# DAC_To_LP_Filter.net
KiCad netlist of a schematic drawn in Altium Designer
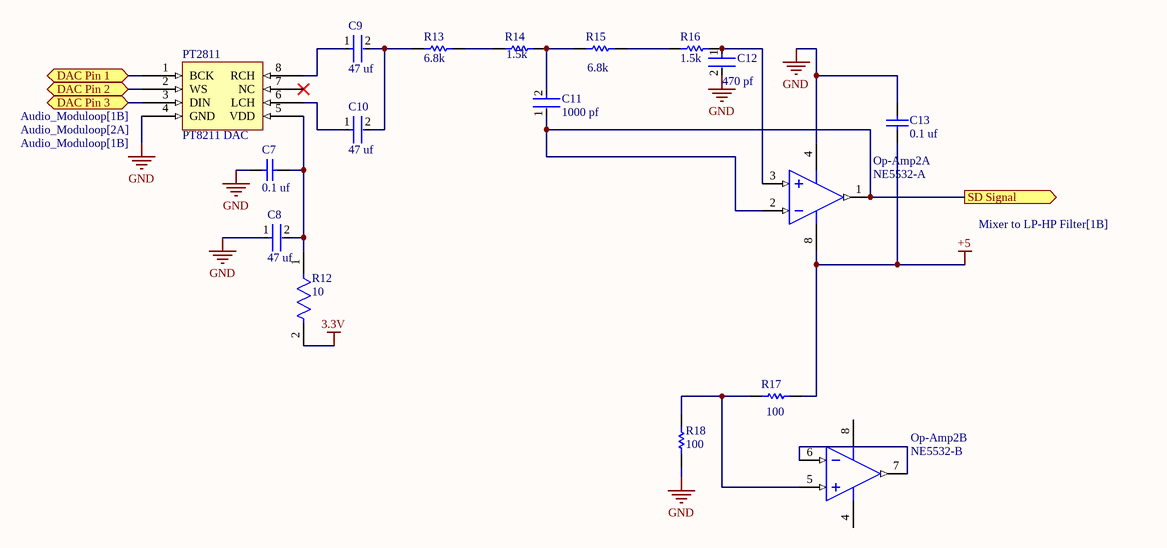
[diagram p0: DAC To LP Filter.SchDoc]

(export (version "E")
  (design (tool "Eeschema 10.0.6"))
  (components
    (comp (ref "C7")
      (value "0.1 uf")
      (footprint "VISH-K104K15X7RF5TL2")
      (description "Ceramic Capacitor, 100 nF, +/- 10%, 50 V, -55 to 125 degC, 2-Pin THD, RoHS, Tape and Reel")
      (fields (field (name "MANUFACTURER") "Vishay") (field (name "TOLERANCE") "±10%"))
      (libsource (lib "Altium Content Vault") (part "CAP-NP-2"))
    )
    (comp (ref "C8")
      (value "47 uf")
      (footprint "FP-RCE2A2-MFG")
      (description "Cap Ceramic 4.7uF 25V X7R ±10% Radial 2.5mm +125°C Automotive Ammo Pack")
      (fields (field (name "TOLERANCE") "10%"))
      (libsource (lib "Altium Content Vault") (part "b4654b650e69147ec39a6b967a45e02"))
    )
    (comp (ref "C9")
      (value "47 uf")
      (footprint "FP-RCE2A2-MFG")
      (description "Cap Ceramic 4.7uF 25V X7R ±10% Radial 2.5mm +125°C Automotive Ammo Pack")
      (fields (field (name "TOLERANCE") "10%"))
      (libsource (lib "Altium Content Vault") (part "b4654b650e69147ec39a6b967a45e02"))
    )
    (comp (ref "C10")
      (value "47 uf")
      (footprint "FP-RCE2A2-MFG")
      (description "Cap Ceramic 4.7uF 25V X7R ±10% Radial 2.5mm +125°C Automotive Ammo Pack")
      (fields (field (name "TOLERANCE") "10%"))
      (libsource (lib "Altium Content Vault") (part "b4654b650e69147ec39a6b967a45e02"))
    )
    (comp (ref "C11")
      (value "1000 pf")
      (footprint "FP-VY1102M35Y5UQ6TV0-MFG")
      (description "CAP CER 1000PF 760VAC Y5U RADIAL")
      (fields (field (name "VOLTAGE") "500V") (field (name "TOLERANCE") "20%"))
      (libsource (lib "Altium Content Vault") (part "6d4d395cd7362dd47ce0157d173177e"))
    )
    (comp (ref "C12")
      (value "470 pf")
      (footprint "FP-F471K33Y5RP6UK5R-MFG")
      (description "CAP CER 470PF 2KV Y5R RADIAL")
      (fields (field (name "TOLERANCE") "10%") (field (name "VOLTAGE") "2kV"))
      (libsource (lib "Altium Content Vault") (part "b4654b650e69147ec39a6b967a45e02"))
    )
    (comp (ref "C13")
      (value "0.1 uf")
      (footprint "AVX-SA115C104KAR")
      (fields (field (name "TOLERANCE") "±10%") (field (name "MANUFACTURER") "AVX"))
      (libsource (lib "Altium Content Vault") (part "CAP-NP-2"))
    )
    (comp (ref "Op-Amp2")
      (value "NE5532-A")
      (footprint "ONSC-SOIC-8-751-07_V")
      (fields (field (name "MANUFACTURER") "On Semiconductor") (field (name "PARTNUMBER") "NE5532AD8R2G"))
      (libsource (lib "Altium Content Vault") (part "ONSC-NE5532-SOIC-8-751-07"))
    )
    (comp (ref "PT2811")
      (value "PT8211 DAC")
      (footprint "SOIC127P602X173-8N")
      (libsource (lib "Ryamgordon") (part "DAC"))
    )
    (comp (ref "R12")
      (value "10")
      (footprint "FP-RN732A-MFG")
      (description "SMD Chip Resistor, Thin Film, 10Ω, 100 V, 0805 [2012 Metric], 100 mW, 0.1%, RN73 Series")
      (fields
        (field (name "MANUFACTURER") "TE Connectivity")
        (field (name "MANUFACTURER PART NUMBER") "RN73C2A10RBTG")
      )
      (libsource (lib "Altium Content Vault") (part "1029c3af85768c4190bb7ad29bc67b5"))
    )
    (comp (ref "R13")
      (value "6.8k")
      (footprint "RESC2013X70X40LL20T20")
      (fields (field (name "MANUFACTURER") "Panasonic") (field (name "PART NUMBER") "ERJ6ENF6801V"))
      (libsource (lib "Altium Content Vault") (part "RES"))
    )
    (comp (ref "R14")
      (value "1.5k")
      (footprint "RESC2013X60X35LL10T20")
      (description "RES 1.50K OHM 1/8W 1% 0805 SMD")
      (fields (field (name "MANUFACTURER") "Yageo") (field (name "PARTNUMBER") "RC0805FR-071K5L"))
      (libsource (lib "Altium Content Vault") (part "RES-2"))
    )
    (comp (ref "R15")
      (value "6.8k")
      (footprint "RESC2013X70X40LL20T20")
      (fields (field (name "MANUFACTURER") "Panasonic") (field (name "PART NUMBER") "ERJ6ENF6801V"))
      (libsource (lib "Altium Content Vault") (part "RES"))
    )
    (comp (ref "R16")
      (value "1.5k")
      (footprint "RESC2013X60X35LL10T20")
      (description "RES 1.50K OHM 1/8W 1% 0805 SMD")
      (fields (field (name "MANUFACTURER") "Yageo") (field (name "PARTNUMBER") "RC0805FR-071K5L"))
      (libsource (lib "Altium Content Vault") (part "RES-2"))
    )
    (comp (ref "R17")
      (value "100")
      (footprint "RESC2013X60X40ML20T25")
      (fields (field (name "MANUFACTURER") "Panasonic") (field (name "PART NUMBER") "ERA6AEB101V"))
      (libsource (lib "Altium Content Vault") (part "RES"))
    )
    (comp (ref "R18")
      (value "100")
      (footprint "RESC2013X60X40ML20T25")
      (fields (field (name "MANUFACTURER") "Panasonic") (field (name "PART NUMBER") "ERA6AEB101V"))
      (libsource (lib "Altium Content Vault") (part "RES"))
    )
  )
  (nets
    (net (code "1") (name "+5") (class "Default")
      (node (ref "C13") (pin "1") (pinfunction "1_1") (pintype "passive"))
      (node (ref "Op-Amp2") (pin "8") (pinfunction "V+_8") (pintype "power_in"))
      (node (ref "R17") (pin "2") (pinfunction "2_2") (pintype "passive"))
    )
    (net (code "2") (name "/DAC Pin 1") (class "Default")
      (node (ref "PT2811") (pin "1") (pinfunction "BCK_1") (pintype "input"))
    )
    (net (code "3") (name "/DAC Pin 2") (class "Default")
      (node (ref "PT2811") (pin "2") (pinfunction "WS_2") (pintype "input"))
    )
    (net (code "4") (name "/DAC Pin 3") (class "Default")
      (node (ref "PT2811") (pin "3") (pinfunction "DIN_3") (pintype "input"))
    )
    (net (code "5") (name "/SD Signal") (class "Default")
      (node (ref "C11") (pin "1") (pinfunction "1_1") (pintype "passive"))
      (node (ref "Op-Amp2") (pin "1") (pinfunction "OUTA_1") (pintype "output"))
      (node (ref "Op-Amp2") (pin "2") (pinfunction "INA-_2") (pintype "input"))
    )
    (net (code "6") (name "3.3V") (class "Default")
      (node (ref "R12") (pin "2") (pinfunction "2_2") (pintype "passive"))
    )
    (net (code "7") (name "GND") (class "Default")
      (node (ref "C12") (pin "2") (pinfunction "2_2") (pintype "passive"))
      (node (ref "C13") (pin "2") (pinfunction "2_2") (pintype "passive"))
      (node (ref "C7") (pin "2") (pinfunction "2_2") (pintype "passive"))
      (node (ref "C8") (pin "1") (pinfunction "1_1") (pintype "passive"))
      (node (ref "Op-Amp2") (pin "4") (pinfunction "V-_4") (pintype "power_in"))
      (node (ref "PT2811") (pin "4") (pinfunction "GND_4") (pintype "input"))
      (node (ref "R18") (pin "1") (pinfunction "1_1") (pintype "passive"))
    )
    (net (code "8") (name "Net-(C10-Pad2)") (class "Default")
      (node (ref "C10") (pin "2") (pinfunction "2_2") (pintype "passive"))
      (node (ref "C9") (pin "2") (pinfunction "2_2") (pintype "passive"))
      (node (ref "R13") (pin "1") (pinfunction "1_1") (pintype "passive"))
    )
    (net (code "9") (name "Net-(C11-Pad2)") (class "Default")
      (node (ref "C11") (pin "2") (pinfunction "2_2") (pintype "passive"))
      (node (ref "R14") (pin "2") (pinfunction "2_2") (pintype "passive"))
      (node (ref "R15") (pin "1") (pinfunction "1_1") (pintype "passive"))
    )
    (net (code "10") (name "Net-(Op-Amp2A-INA+)") (class "Default")
      (node (ref "C12") (pin "1") (pinfunction "1_1") (pintype "passive"))
      (node (ref "Op-Amp2") (pin "3") (pinfunction "INA+_3") (pintype "input"))
      (node (ref "R16") (pin "2") (pinfunction "2_2") (pintype "passive"))
    )
    (net (code "11") (name "Net-(Op-Amp2B-INB+)") (class "Default")
      (node (ref "Op-Amp2") (pin "5") (pinfunction "INB+_5") (pintype "input"))
      (node (ref "R17") (pin "1") (pinfunction "1_1") (pintype "passive"))
      (node (ref "R18") (pin "2") (pinfunction "2_2") (pintype "passive"))
    )
    (net (code "12") (name "Net-(Op-Amp2B-INB-)") (class "Default")
      (node (ref "Op-Amp2") (pin "6") (pinfunction "INB-_6") (pintype "input"))
      (node (ref "Op-Amp2") (pin "7") (pinfunction "OUTB_7") (pintype "output"))
    )
    (net (code "13") (name "Net-(PT2811-LCH)") (class "Default")
      (node (ref "C10") (pin "1") (pinfunction "1_1") (pintype "passive"))
      (node (ref "PT2811") (pin "6") (pinfunction "LCH_6") (pintype "input"))
    )
    (net (code "14") (name "Net-(PT2811-RCH)") (class "Default")
      (node (ref "C9") (pin "1") (pinfunction "1_1") (pintype "passive"))
      (node (ref "PT2811") (pin "8") (pinfunction "RCH_8") (pintype "input"))
    )
    (net (code "15") (name "Net-(PT2811-VDD)") (class "Default")
      (node (ref "C7") (pin "1") (pinfunction "1_1") (pintype "passive"))
      (node (ref "C8") (pin "2") (pinfunction "2_2") (pintype "passive"))
      (node (ref "PT2811") (pin "5") (pinfunction "VDD_5") (pintype "input"))
      (node (ref "R12") (pin "1") (pinfunction "1_1") (pintype "passive"))
    )
    (net (code "16") (name "Net-(R13-Pad2)") (class "Default")
      (node (ref "R13") (pin "2") (pinfunction "2_2") (pintype "passive"))
      (node (ref "R14") (pin "1") (pinfunction "1_1") (pintype "passive"))
    )
    (net (code "17") (name "Net-(R15-Pad2)") (class "Default")
      (node (ref "R15") (pin "2") (pinfunction "2_2") (pintype "passive"))
      (node (ref "R16") (pin "1") (pinfunction "1_1") (pintype "passive"))
    )
    (net (code "18") (name "unconnected-(Op-Amp2B-V+-Pad8)") (class "Default")
      (node (ref "Op-Amp2") (pin "8") (pinfunction "V+_8") (pintype "power_in"))
    )
    (net (code "19") (name "unconnected-(Op-Amp2B-V--Pad4)") (class "Default")
      (node (ref "Op-Amp2") (pin "4") (pinfunction "V-_4") (pintype "power_in"))
    )
    (net (code "20") (name "unconnected-(PT2811-NC-Pad7)") (class "Default")
      (node (ref "PT2811") (pin "7") (pinfunction "NC_7") (pintype "input+no_connect"))
    )
  )
)
